# SENSORS.net
KiCad netlist of a schematic drawn in Altium Designer
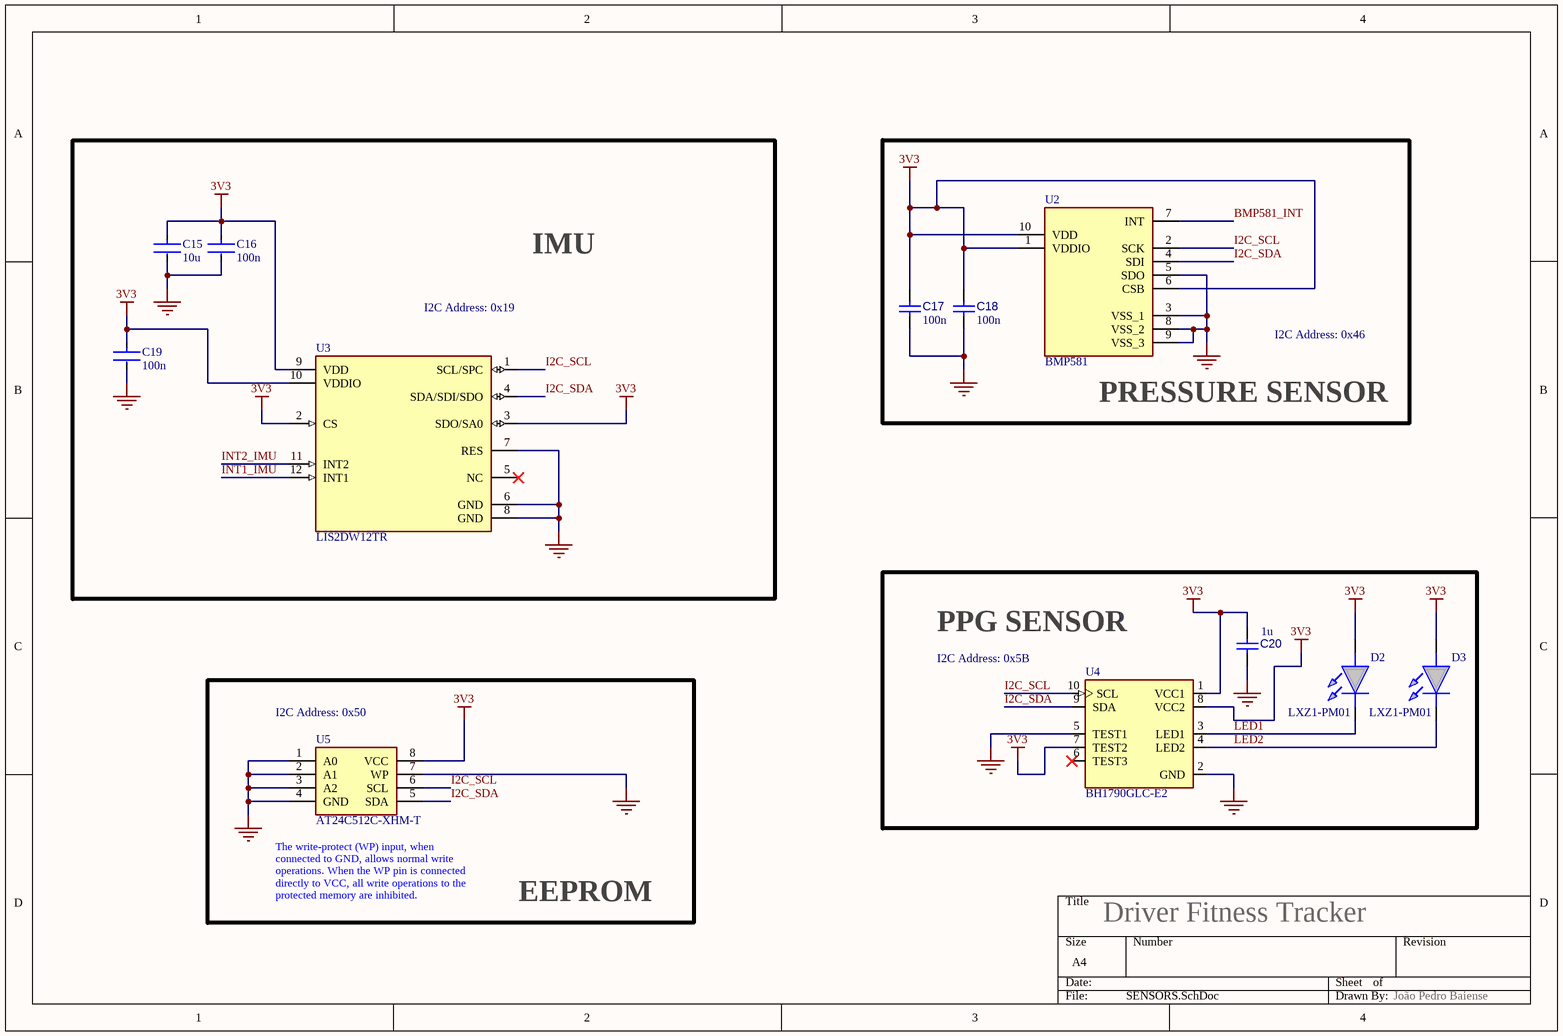
[diagram p0: SENSORS.SchDoc]

(export (version "E")
  (design (tool "Eeschema 10.0.6"))
  (components
    (comp (ref "C15")
      (value "10u")
      (footprint "FP-C0402-BB-MFG")
      (description "Multilayer Ceramic Capacitors MLCC - SMD/SMT 10 uF 6.3 VDC 20% 0402 X5R")
      (fields (field (name "MANUFACTURER") "Kemet") (field (name "TOLERANCE") "0.1"))
      (libsource (lib "Altium Content Vault") (part "b4654b650e69147ec39a6b967a45e02"))
    )
    (comp (ref "C16")
      (value "100n")
      (footprint "FP-C0402-BB-MFG")
      (description "Multilayer Ceramic Capacitors MLCC - SMD/SMT NEW GLOBAL PN KGM05CR71H104KN 50V 0.1uF X7R 0402 10%")
      (fields (field (name "MANUFACTURER") "Kemet") (field (name "TOLERANCE") "0.1"))
      (libsource (lib "Altium Content Vault") (part "b4654b650e69147ec39a6b967a45e02"))
    )
    (comp (ref "C17")
      (value "100n")
      (footprint "CAPC1608X90X40NL10T20")
      (description "Multilayer Ceramic Capacitors MLCC - SMD/SMT 50V 0.1 uF X7R 0603 10% AEC-Q200")
      (fields (field (name "TOLERANCE") "10%") (field (name "JLCPCB PART #") "C1523"))
      (libsource (lib "Tese_project") (part "CAP-NP-2"))
    )
    (comp (ref "C18")
      (value "100n")
      (footprint "CAPC1608X90X40NL10T20")
      (description "Multilayer Ceramic Capacitors MLCC - SMD/SMT 50V 0.1 uF X7R 0603 10% AEC-Q200")
      (fields (field (name "TOLERANCE") "10%") (field (name "JLCPCB PART #") "C1523"))
      (libsource (lib "Tese_project") (part "CAP-NP-2"))
    )
    (comp (ref "C19")
      (value "100n")
      (footprint "FP-C0402-BB-MFG")
      (description "Multilayer Ceramic Capacitors MLCC - SMD/SMT NEW GLOBAL PN KGM05CR71H104KN 50V 0.1uF X7R 0402 10%")
      (fields (field (name "MANUFACTURER") "Kemet") (field (name "TOLERANCE") "0.1"))
      (libsource (lib "Altium Content Vault") (part "b4654b650e69147ec39a6b967a45e02"))
    )
    (comp (ref "C20")
      (value "1u")
      (footprint "CAPC1608X90X40NL10T20")
      (description "Multilayer Ceramic Capacitors MLCC - SMD/SMT 50V 1uF X7R 0603 10%")
      (fields (field (name "TOLERANCE") "10%") (field (name "JLCPCB PART #") "C15849"))
      (libsource (lib "Tese_project") (part "CAP-NP-2"))
    )
    (comp (ref "D2")
      (value "LXZ1-PM01")
      (footprint "LEDC1608X70N")
      (description "Standard LEDs - SMD Brilliant Green Everlight")
      (fields
        (field (name "MOUSER PART NUMBER") "638-19217GHCYR1S23T")
        (field (name "JLCPCB PART #") "C72043")
      )
      (libsource (lib "Tese_SymbolLib") (part "LED_19-217/GHC-YR1S2/3T"))
    )
    (comp (ref "D3")
      (value "LXZ1-PM01")
      (footprint "LEDC1608X70N")
      (description "High Power LEDs - Single Color Green")
      (fields
        (field (name "MOUSER PART NUMBER") "638-19217GHCYR1S23T")
        (field (name "JLCPCB PART #") "C72043")
      )
      (libsource (lib "Tese_SymbolLib") (part "LED_19-217/GHC-YR1S2/3T"))
    )
    (comp (ref "U2")
      (value "BMP581")
      (footprint "BMP581")
      (fields (field (name "MOUSER PART NUMBER") "262-BMP581"))
      (libsource (lib "Tese_SymbolLib") (part "BMP581"))
    )
    (comp (ref "U3")
      (value "LIS2DW12TR")
      (footprint "FP-LGA12-DM00170568-MFG")
      (description "ACCEL 2-16G I2C/SPI 12LGA STMicroelectronics")
      (fields
        (field (name "OCTOPART") "https://octopart.com/lis2dw12tr-stmicroelectronics-77080925")
        (field (name "MANUFACTURER") "STMicroelectronics")
      )
      (libsource (lib "Tese_SymbolLib") (part "CMP-12175-000006-1"))
    )
    (comp (ref "U4")
      (value "BH1790GLC-E2")
      (footprint "PQFN70P280X280X100-10N")
      (description "Light To Frequency & Light To Voltage Opt Sensr Heart Rate Monitor IC 200uA")
      (fields (field (name "MF") "Rohm"))
      (libsource (lib "Tese_SymbolLib") (part "BH1790GLC-E2"))
    )
    (comp (ref "U5")
      (value "AT24C512C-XHM-T")
      (footprint "SOP65P640X120-8N")
      (description "EEPROM SERIAL EEPROM 512K (64K X 8) 2WIRE 1.7V")
      (fields
        (field (name "MOUSER PART NUMBER") "556-AT24C512C-XHM-T")
        (field (name "JLCPCB PART #") "C111546")
      )
      (libsource (lib "Tese_SymbolLib") (part "AT24C512C-XHM-T"))
    )
  )
  (nets
    (net (code "1") (name "/BMP581_INT") (class "Default")
      (node (ref "U2") (pin "7") (pinfunction "INT_7") (pintype "passive"))
    )
    (net (code "2") (name "/I2C_SCL") (class "Default")
      (node (ref "U2") (pin "2") (pinfunction "SCK_2") (pintype "passive"))
      (node (ref "U3") (pin "1") (pinfunction "SCL/SPC_1") (pintype "bidirectional"))
      (node (ref "U4") (pin "10") (pinfunction "SCL_10") (pintype "input"))
      (node (ref "U5") (pin "6") (pinfunction "SCL_6") (pintype "passive"))
    )
    (net (code "3") (name "/I2C_SDA") (class "Default")
      (node (ref "U2") (pin "4") (pinfunction "SDI_4") (pintype "passive"))
      (node (ref "U3") (pin "4") (pinfunction "SDA/SDI/SDO_4") (pintype "bidirectional"))
      (node (ref "U4") (pin "9") (pinfunction "SDA_9") (pintype "bidirectional"))
      (node (ref "U5") (pin "5") (pinfunction "SDA_5") (pintype "passive"))
    )
    (net (code "4") (name "/INT1_IMU") (class "Default")
      (node (ref "U3") (pin "12") (pinfunction "INT1_12") (pintype "input"))
    )
    (net (code "5") (name "/INT2_IMU") (class "Default")
      (node (ref "U3") (pin "11") (pinfunction "INT2_11") (pintype "input"))
    )
    (net (code "6") (name "/LED1") (class "Default")
      (node (ref "D2") (pin "1") (pinfunction "K_1") (pintype "passive"))
      (node (ref "U4") (pin "3") (pinfunction "LED1_3") (pintype "passive"))
    )
    (net (code "7") (name "/LED2") (class "Default")
      (node (ref "D3") (pin "1") (pinfunction "K_1") (pintype "passive"))
      (node (ref "U4") (pin "4") (pinfunction "LED2_4") (pintype "passive"))
    )
    (net (code "8") (name "3V3") (class "Default")
      (node (ref "C15") (pin "1") (pinfunction "1_1") (pintype "passive"))
      (node (ref "C16") (pin "1") (pinfunction "1_1") (pintype "passive"))
      (node (ref "C17") (pin "2") (pinfunction "2_2") (pintype "passive"))
      (node (ref "C18") (pin "2") (pinfunction "2_2") (pintype "passive"))
      (node (ref "C19") (pin "1") (pinfunction "1_1") (pintype "passive"))
      (node (ref "C20") (pin "1") (pinfunction "1_1") (pintype "passive"))
      (node (ref "D2") (pin "2") (pinfunction "A_2") (pintype "passive"))
      (node (ref "D3") (pin "2") (pinfunction "A_2") (pintype "passive"))
      (node (ref "U2") (pin "1") (pinfunction "VDDIO_1") (pintype "passive"))
      (node (ref "U2") (pin "10") (pinfunction "VDD_10") (pintype "passive"))
      (node (ref "U2") (pin "6") (pinfunction "CSB_6") (pintype "passive"))
      (node (ref "U3") (pin "10") (pinfunction "VDDIO_10") (pintype "power_in"))
      (node (ref "U3") (pin "2") (pinfunction "CS_2") (pintype "input"))
      (node (ref "U3") (pin "3") (pinfunction "SDO/SA0_3") (pintype "bidirectional"))
      (node (ref "U3") (pin "9") (pinfunction "VDD_9") (pintype "power_in"))
      (node (ref "U4") (pin "1") (pinfunction "VCC1_1") (pintype "power_in"))
      (node (ref "U4") (pin "7") (pinfunction "TEST2_7") (pintype "passive"))
      (node (ref "U4") (pin "8") (pinfunction "VCC2_8") (pintype "power_in"))
      (node (ref "U5") (pin "8") (pinfunction "VCC_8") (pintype "passive"))
    )
    (net (code "9") (name "GND") (class "Default")
      (node (ref "C15") (pin "2") (pinfunction "2_2") (pintype "passive"))
      (node (ref "C16") (pin "2") (pinfunction "2_2") (pintype "passive"))
      (node (ref "C17") (pin "1") (pinfunction "1_1") (pintype "passive"))
      (node (ref "C18") (pin "1") (pinfunction "1_1") (pintype "passive"))
      (node (ref "C19") (pin "2") (pinfunction "2_2") (pintype "passive"))
      (node (ref "C20") (pin "2") (pinfunction "2_2") (pintype "passive"))
      (node (ref "U2") (pin "3") (pinfunction "VSS_1_3") (pintype "passive"))
      (node (ref "U2") (pin "5") (pinfunction "SDO_5") (pintype "passive"))
      (node (ref "U2") (pin "8") (pinfunction "VSS_2_8") (pintype "passive"))
      (node (ref "U2") (pin "9") (pinfunction "VSS_3_9") (pintype "passive"))
      (node (ref "U3") (pin "6") (pinfunction "GND_6") (pintype "power_in"))
      (node (ref "U3") (pin "7") (pinfunction "RES_7") (pintype "passive"))
      (node (ref "U3") (pin "8") (pinfunction "GND_8") (pintype "power_in"))
      (node (ref "U4") (pin "2") (pinfunction "GND_2") (pintype "power_in"))
      (node (ref "U4") (pin "5") (pinfunction "TEST1_5") (pintype "passive"))
      (node (ref "U5") (pin "1") (pinfunction "A0_1") (pintype "passive"))
      (node (ref "U5") (pin "2") (pinfunction "A1_2") (pintype "passive"))
      (node (ref "U5") (pin "3") (pinfunction "A2_3") (pintype "passive"))
      (node (ref "U5") (pin "4") (pinfunction "GND_4") (pintype "passive"))
      (node (ref "U5") (pin "7") (pinfunction "WP_7") (pintype "passive"))
    )
    (net (code "10") (name "unconnected-(U3-NC-Pad5)") (class "Default")
      (node (ref "U3") (pin "5") (pinfunction "NC_5") (pintype "passive+no_connect"))
    )
    (net (code "11") (name "unconnected-(U4-TEST3-Pad6)") (class "Default")
      (node (ref "U4") (pin "6") (pinfunction "TEST3_6") (pintype "passive+no_connect"))
    )
  )
)
